# v2.net
KiCad netlist of a schematic drawn in EAGLE
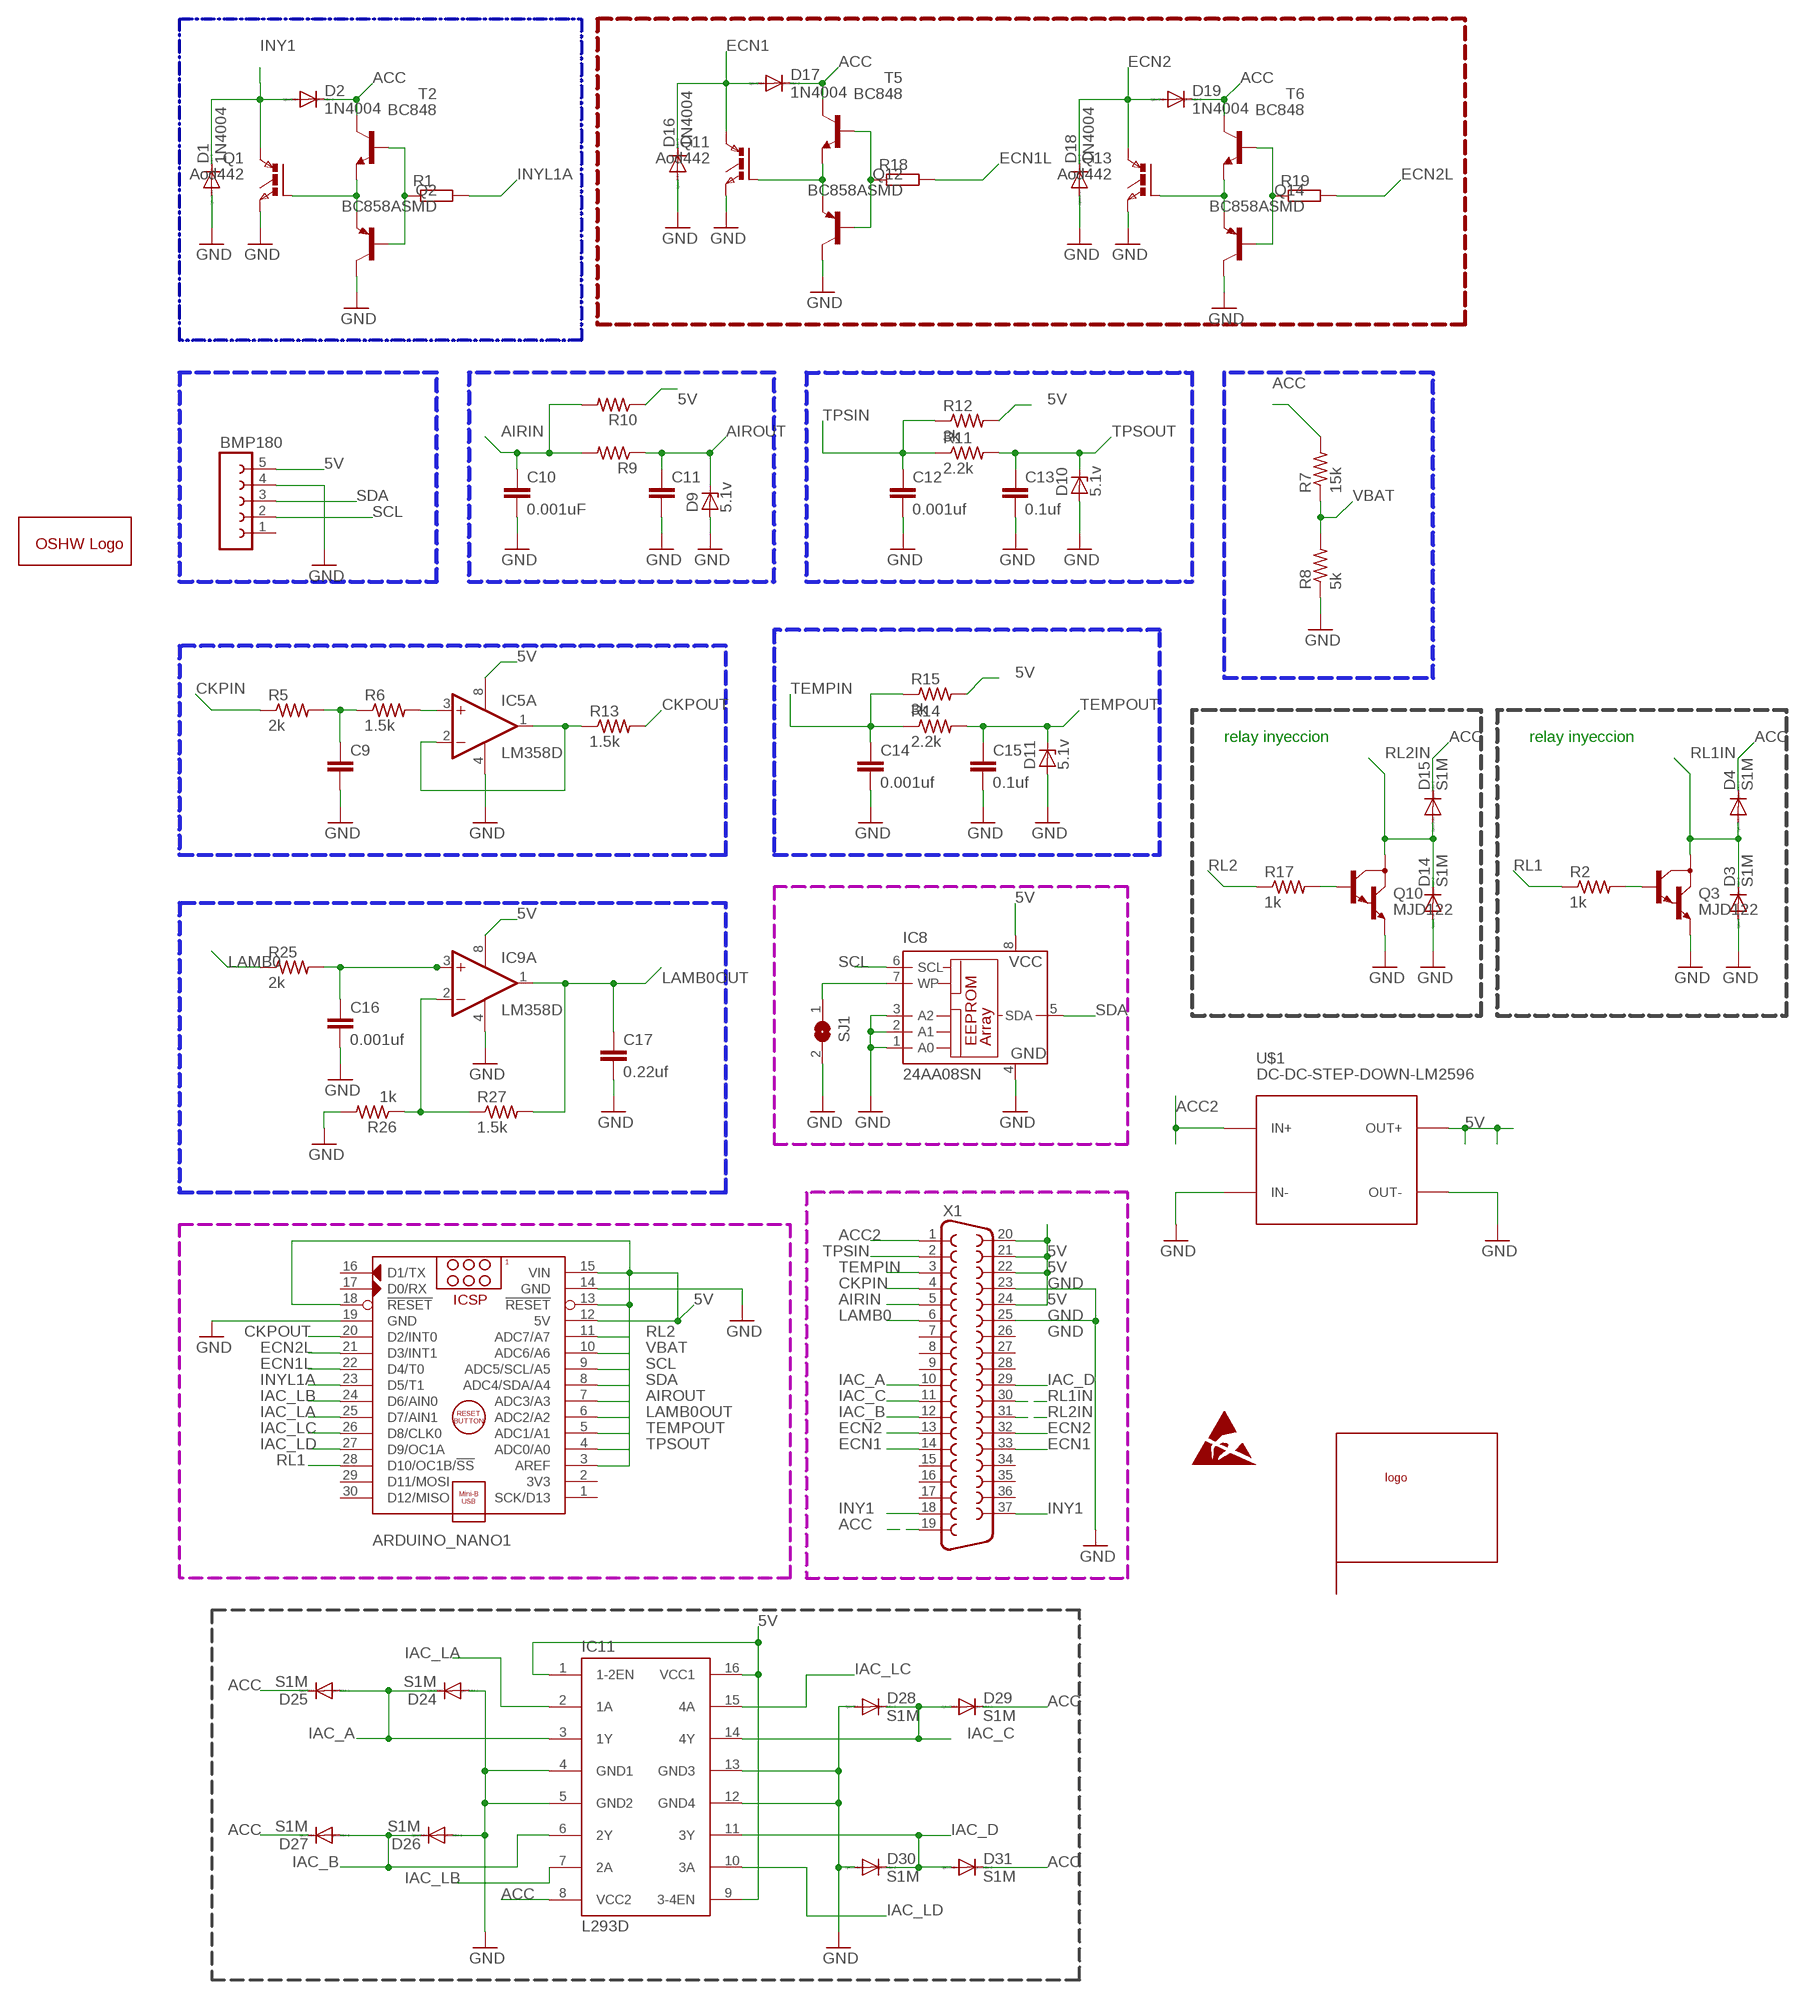
[diagram p0: schematic, sheet 1]

(export (version "E")
  (design (tool "Eeschema 10.0.6"))
  (components
    (comp (ref "ARDUINO_NANO1")
      (value "ARDUINO_NANO")
      (footprint "eagle-import:ARDUINO_NANO")
      (libsource (lib "eagle-import") (part "ARDUINO_NANO"))
    )
    (comp (ref "BMP180")
      (value "FE05-1")
      (footprint "eagle-import:FE05-1")
      (libsource (lib "eagle-import") (part "FE05-1"))
    )
    (comp (ref "C9")
      (value "C-EU025-025X050")
      (footprint "eagle-import:C025-025X050")
      (libsource (lib "eagle-import") (part "C-EU025-025X050"))
    )
    (comp (ref "C10")
      (value "0.001uF")
      (footprint "eagle-import:C025-025X050")
      (libsource (lib "eagle-import") (part "C-EU025-025X050"))
    )
    (comp (ref "C11")
      (value "C-EU025-025X050")
      (footprint "eagle-import:C025-025X050")
      (libsource (lib "eagle-import") (part "C-EU025-025X050"))
    )
    (comp (ref "C12")
      (value "0.001uf")
      (footprint "eagle-import:C025-025X050")
      (libsource (lib "eagle-import") (part "C-EU025-025X050"))
    )
    (comp (ref "C13")
      (value "0.1uf")
      (footprint "eagle-import:C025-025X050")
      (libsource (lib "eagle-import") (part "C-EU025-025X050"))
    )
    (comp (ref "C14")
      (value "0.001uf")
      (footprint "eagle-import:C025-025X050")
      (libsource (lib "eagle-import") (part "C-EU025-025X050"))
    )
    (comp (ref "C15")
      (value "0.1uf")
      (footprint "eagle-import:C025-025X050")
      (libsource (lib "eagle-import") (part "C-EU025-025X050"))
    )
    (comp (ref "C16")
      (value "0.001uf")
      (footprint "eagle-import:C025-025X050")
      (libsource (lib "eagle-import") (part "C-EU025-025X050"))
    )
    (comp (ref "C17")
      (value "0.22uf")
      (footprint "eagle-import:C025-025X050")
      (libsource (lib "eagle-import") (part "C-EU025-025X050"))
    )
    (comp (ref "D1")
      (value "1N4004")
      (footprint "eagle-import:DO41-10")
      (libsource (lib "eagle-import") (part "1N4004"))
    )
    (comp (ref "D2")
      (value "1N4004")
      (footprint "eagle-import:DO41-10")
      (libsource (lib "eagle-import") (part "1N4004"))
    )
    (comp (ref "D3")
      (value "S1M")
      (footprint "eagle-import:SMA")
      (libsource (lib "eagle-import") (part "S1M"))
    )
    (comp (ref "D4")
      (value "S1M")
      (footprint "eagle-import:SMA")
      (libsource (lib "eagle-import") (part "S1M"))
    )
    (comp (ref "D9")
      (value "5.1v")
      (footprint "eagle-import:ZDIO-5")
      (libsource (lib "eagle-import") (part "ZENER-DIODEZD-5"))
    )
    (comp (ref "D10")
      (value "5.1v")
      (footprint "eagle-import:ZDIO-5")
      (libsource (lib "eagle-import") (part "ZENER-DIODEZD-5"))
    )
    (comp (ref "D11")
      (value "5.1v")
      (footprint "eagle-import:ZDIO-5")
      (libsource (lib "eagle-import") (part "ZENER-DIODEZD-5"))
    )
    (comp (ref "D14")
      (value "S1M")
      (footprint "eagle-import:SMA")
      (libsource (lib "eagle-import") (part "S1M"))
    )
    (comp (ref "D15")
      (value "S1M")
      (footprint "eagle-import:SMA")
      (libsource (lib "eagle-import") (part "S1M"))
    )
    (comp (ref "D16")
      (value "1N4004")
      (footprint "eagle-import:DO41-10")
      (libsource (lib "eagle-import") (part "1N4004"))
    )
    (comp (ref "D17")
      (value "1N4004")
      (footprint "eagle-import:DO41-10")
      (libsource (lib "eagle-import") (part "1N4004"))
    )
    (comp (ref "D18")
      (value "1N4004")
      (footprint "eagle-import:DO41-10")
      (libsource (lib "eagle-import") (part "1N4004"))
    )
    (comp (ref "D19")
      (value "1N4004")
      (footprint "eagle-import:DO41-10")
      (libsource (lib "eagle-import") (part "1N4004"))
    )
    (comp (ref "D24")
      (value "S1M")
      (footprint "eagle-import:SMA")
      (libsource (lib "eagle-import") (part "S1M"))
    )
    (comp (ref "D25")
      (value "S1M")
      (footprint "eagle-import:SMA")
      (libsource (lib "eagle-import") (part "S1M"))
    )
    (comp (ref "D26")
      (value "S1M")
      (footprint "eagle-import:SMA")
      (libsource (lib "eagle-import") (part "S1M"))
    )
    (comp (ref "D27")
      (value "S1M")
      (footprint "eagle-import:SMA")
      (libsource (lib "eagle-import") (part "S1M"))
    )
    (comp (ref "D28")
      (value "S1M")
      (footprint "eagle-import:SMA")
      (libsource (lib "eagle-import") (part "S1M"))
    )
    (comp (ref "D29")
      (value "S1M")
      (footprint "eagle-import:SMA")
      (libsource (lib "eagle-import") (part "S1M"))
    )
    (comp (ref "D30")
      (value "S1M")
      (footprint "eagle-import:SMA")
      (libsource (lib "eagle-import") (part "S1M"))
    )
    (comp (ref "D31")
      (value "S1M")
      (footprint "eagle-import:SMA")
      (libsource (lib "eagle-import") (part "S1M"))
    )
    (comp (ref "GOLD_ORB_SM1")
      (value "OSHWLOGOLOGO8MM")
      (footprint "eagle-import:OSHW_8MM")
      (libsource (lib "eagle-import") (part "OSHWLOGOLOGO8MM"))
    )
    (comp (ref "IC5")
      (value "LM358D")
      (footprint "eagle-import:SO08")
      (libsource (lib "eagle-import") (part "LM358D"))
    )
    (comp (ref "IC8")
      (value "24AA08SN")
      (footprint "eagle-import:SO-08")
      (fields (field (name "MF") "MICROCHIP") (field (name "MPN") "24AA08-I/SN"))
      (libsource (lib "eagle-import") (part "24SNAA08"))
    )
    (comp (ref "IC9")
      (value "LM358D")
      (footprint "eagle-import:SO08")
      (libsource (lib "eagle-import") (part "LM358D"))
    )
    (comp (ref "IC11")
      (value "L293D")
      (footprint "eagle-import:DIL16")
      (libsource (lib "eagle-import") (part "L293D"))
    )
    (comp (ref "Q1")
      (value "Aod442")
      (footprint "eagle-import:TO252")
      (libsource (lib "eagle-import") (part "IGBTTO252"))
    )
    (comp (ref "Q2")
      (value "BC858ASMD")
      (footprint "eagle-import:SOT23-BEC")
      (libsource (lib "eagle-import") (part "BC858SMDA"))
    )
    (comp (ref "Q3")
      (value "MJD122")
      (footprint "eagle-import:DPAK")
      (fields (field (name "MF") "STMicroelectronics"))
      (libsource (lib "eagle-import") (part "MJD122"))
    )
    (comp (ref "Q10")
      (value "MJD122")
      (footprint "eagle-import:DPAK")
      (fields (field (name "MF") "STMicroelectronics"))
      (libsource (lib "eagle-import") (part "MJD122"))
    )
    (comp (ref "Q11")
      (value "Aod442")
      (footprint "eagle-import:TO252")
      (libsource (lib "eagle-import") (part "IGBTTO252"))
    )
    (comp (ref "Q12")
      (value "BC858ASMD")
      (footprint "eagle-import:SOT23-BEC")
      (libsource (lib "eagle-import") (part "BC858SMDA"))
    )
    (comp (ref "Q13")
      (value "Aod442")
      (footprint "eagle-import:TO252")
      (libsource (lib "eagle-import") (part "IGBTTO252"))
    )
    (comp (ref "Q14")
      (value "BC858ASMD")
      (footprint "eagle-import:SOT23-BEC")
      (libsource (lib "eagle-import") (part "BC858SMDA"))
    )
    (comp (ref "R1")
      (value "R-EU_0204/7")
      (footprint "eagle-import:0204_7")
      (libsource (lib "eagle-import") (part "R-EU_0204/7"))
    )
    (comp (ref "R2")
      (value "1k")
      (footprint "eagle-import:0204_5")
      (libsource (lib "eagle-import") (part "R-US_0204/5"))
    )
    (comp (ref "R5")
      (value "2k")
      (footprint "eagle-import:0204_5")
      (libsource (lib "eagle-import") (part "R-US_0204/5"))
    )
    (comp (ref "R6")
      (value "1.5k")
      (footprint "eagle-import:0204_5")
      (libsource (lib "eagle-import") (part "R-US_0204/5"))
    )
    (comp (ref "R7")
      (value "15k")
      (footprint "eagle-import:0204_5")
      (libsource (lib "eagle-import") (part "R-US_0204/5"))
    )
    (comp (ref "R8")
      (value "5k")
      (footprint "eagle-import:0204_5")
      (libsource (lib "eagle-import") (part "R-US_0204/5"))
    )
    (comp (ref "R9")
      (value "R-US_0204/5")
      (footprint "eagle-import:0204_5")
      (libsource (lib "eagle-import") (part "R-US_0204/5"))
    )
    (comp (ref "R10")
      (value "R-US_0204/5")
      (footprint "eagle-import:0204_5")
      (libsource (lib "eagle-import") (part "R-US_0204/5"))
    )
    (comp (ref "R11")
      (value "2.2k")
      (footprint "eagle-import:0204_5")
      (libsource (lib "eagle-import") (part "R-US_0204/5"))
    )
    (comp (ref "R12")
      (value "3k")
      (footprint "eagle-import:0204_5")
      (libsource (lib "eagle-import") (part "R-US_0204/5"))
    )
    (comp (ref "R13")
      (value "1.5k")
      (footprint "eagle-import:0204_5")
      (libsource (lib "eagle-import") (part "R-US_0204/5"))
    )
    (comp (ref "R14")
      (value "2.2k")
      (footprint "eagle-import:0204_5")
      (libsource (lib "eagle-import") (part "R-US_0204/5"))
    )
    (comp (ref "R15")
      (value "3k")
      (footprint "eagle-import:0204_5")
      (libsource (lib "eagle-import") (part "R-US_0204/5"))
    )
    (comp (ref "R17")
      (value "1k")
      (footprint "eagle-import:0204_5")
      (libsource (lib "eagle-import") (part "R-US_0204/5"))
    )
    (comp (ref "R18")
      (value "R-EU_0204/7")
      (footprint "eagle-import:0204_7")
      (libsource (lib "eagle-import") (part "R-EU_0204/7"))
    )
    (comp (ref "R19")
      (value "R-EU_0204/7")
      (footprint "eagle-import:0204_7")
      (libsource (lib "eagle-import") (part "R-EU_0204/7"))
    )
    (comp (ref "R25")
      (value "2k")
      (footprint "eagle-import:0204_5")
      (libsource (lib "eagle-import") (part "R-US_0204/5"))
    )
    (comp (ref "R26")
      (value "1k")
      (footprint "eagle-import:0204_5")
      (libsource (lib "eagle-import") (part "R-US_0204/5"))
    )
    (comp (ref "R27")
      (value "1.5k")
      (footprint "eagle-import:0204_5")
      (libsource (lib "eagle-import") (part "R-US_0204/5"))
    )
    (comp (ref "SJ1")
      (value "SJW")
      (footprint "eagle-import:SJW")
      (libsource (lib "eagle-import") (part "SJW"))
    )
    (comp (ref "T2")
      (value "BC848")
      (footprint "eagle-import:SOT23")
      (libsource (lib "eagle-import") (part "BC848"))
    )
    (comp (ref "T5")
      (value "BC848")
      (footprint "eagle-import:SOT23")
      (libsource (lib "eagle-import") (part "BC848"))
    )
    (comp (ref "T6")
      (value "BC848")
      (footprint "eagle-import:SOT23")
      (libsource (lib "eagle-import") (part "BC848"))
    )
    (comp (ref "U$1")
      (value "DC-DC-STEP-DOWN-LM2596")
      (footprint "eagle-import:DC-DC-STEP-DOWN-LM2596")
      (libsource (lib "eagle-import") (part "DC-DC-STEP-DOWN-LM2596"))
    )
    (comp (ref "U$2")
      (value "LOGO")
      (footprint "eagle-import:LOGO")
      (libsource (lib "eagle-import") (part "LOGO"))
    )
    (comp (ref "X1")
      (value "F37HP")
      (footprint "eagle-import:F37HP")
      (libsource (lib "eagle-import") (part "F37HP"))
    )
  )
  (nets
    (net (code "1") (name "/5V") (class "Default")
      (node (ref "ARDUINO_NANO1") (pin "12") (pinfunction "5V_12") (pintype "power_in"))
      (node (ref "ARDUINO_NANO1") (pin "13") (pinfunction "~{RESET}_13") (pintype "input"))
      (node (ref "ARDUINO_NANO1") (pin "15") (pinfunction "VIN_15") (pintype "power_in"))
      (node (ref "ARDUINO_NANO1") (pin "18") (pinfunction "~{RESET}_18") (pintype "input"))
      (node (ref "ARDUINO_NANO1") (pin "3") (pinfunction "AREF_3") (pintype "input"))
      (node (ref "BMP180") (pin "5") (pinfunction "5_5") (pintype "passive"))
      (node (ref "IC11") (pin "1") (pinfunction "1-2EN_1") (pintype "input"))
      (node (ref "IC11") (pin "16") (pinfunction "VCC1_16") (pintype "power_in"))
      (node (ref "IC11") (pin "9") (pinfunction "3-4EN_9") (pintype "input"))
      (node (ref "IC5") (pin "8") (pinfunction "V+_8") (pintype "power_in"))
      (node (ref "IC8") (pin "8") (pinfunction "VCC_8") (pintype "power_in"))
      (node (ref "IC9") (pin "8") (pinfunction "V+_8") (pintype "power_in"))
      (node (ref "R10") (pin "1") (pinfunction "1_1") (pintype "passive"))
      (node (ref "R12") (pin "2") (pinfunction "2_2") (pintype "passive"))
      (node (ref "R15") (pin "2") (pinfunction "2_2") (pintype "passive"))
      (node (ref "U$1") (pin "OUT+") (pinfunction "OUT+_OUT+") (pintype "bidirectional"))
      (node (ref "X1") (pin "20") (pinfunction "20_20") (pintype "passive"))
      (node (ref "X1") (pin "21") (pinfunction "21_21") (pintype "passive"))
      (node (ref "X1") (pin "22") (pinfunction "22_22") (pintype "passive"))
      (node (ref "X1") (pin "24") (pinfunction "24_24") (pintype "passive"))
    )
    (net (code "2") (name "/ACC") (class "Default")
      (node (ref "D15") (pin "C") (pinfunction "C_C") (pintype "passive"))
      (node (ref "D17") (pin "C") (pinfunction "C_C") (pintype "passive"))
      (node (ref "D19") (pin "C") (pinfunction "C_C") (pintype "passive"))
      (node (ref "D2") (pin "C") (pinfunction "C_C") (pintype "passive"))
      (node (ref "D25") (pin "C") (pinfunction "C_C") (pintype "passive"))
      (node (ref "D27") (pin "C") (pinfunction "C_C") (pintype "passive"))
      (node (ref "D29") (pin "C") (pinfunction "C_C") (pintype "passive"))
      (node (ref "D31") (pin "C") (pinfunction "C_C") (pintype "passive"))
      (node (ref "D4") (pin "C") (pinfunction "C_C") (pintype "passive"))
      (node (ref "IC11") (pin "8") (pinfunction "VCC2_8") (pintype "power_in"))
      (node (ref "R7") (pin "2") (pinfunction "2_2") (pintype "passive"))
      (node (ref "T2") (pin "3") (pinfunction "C_3") (pintype "passive"))
      (node (ref "T5") (pin "3") (pinfunction "C_3") (pintype "passive"))
      (node (ref "T6") (pin "3") (pinfunction "C_3") (pintype "passive"))
      (node (ref "X1") (pin "19") (pinfunction "19_19") (pintype "passive"))
    )
    (net (code "3") (name "/ACC2") (class "Default")
      (node (ref "U$1") (pin "IN+") (pinfunction "IN+_IN+") (pintype "bidirectional"))
      (node (ref "X1") (pin "1") (pinfunction "1_1") (pintype "passive"))
    )
    (net (code "4") (name "/AIRIN") (class "Default")
      (node (ref "C10") (pin "1") (pinfunction "1_1") (pintype "passive"))
      (node (ref "R10") (pin "2") (pinfunction "2_2") (pintype "passive"))
      (node (ref "R9") (pin "2") (pinfunction "2_2") (pintype "passive"))
      (node (ref "X1") (pin "5") (pinfunction "5_5") (pintype "passive"))
    )
    (net (code "5") (name "/AIROUT") (class "Default")
      (node (ref "ARDUINO_NANO1") (pin "7") (pinfunction "ADC3/A3_7") (pintype "bidirectional"))
      (node (ref "C11") (pin "1") (pinfunction "1_1") (pintype "passive"))
      (node (ref "D9") (pin "C") (pinfunction "C_C") (pintype "passive"))
      (node (ref "R9") (pin "1") (pinfunction "1_1") (pintype "passive"))
    )
    (net (code "6") (name "/CKPIN") (class "Default")
      (node (ref "R5") (pin "1") (pinfunction "1_1") (pintype "passive"))
      (node (ref "X1") (pin "4") (pinfunction "4_4") (pintype "passive"))
    )
    (net (code "7") (name "/CKPOUT") (class "Default")
      (node (ref "ARDUINO_NANO1") (pin "20") (pinfunction "D2/INT0_20") (pintype "bidirectional"))
      (node (ref "R13") (pin "2") (pinfunction "2_2") (pintype "passive"))
    )
    (net (code "8") (name "/ECN1") (class "Default")
      (node (ref "D16") (pin "C") (pinfunction "C_C") (pintype "passive"))
      (node (ref "D17") (pin "A") (pinfunction "A_A") (pintype "passive"))
      (node (ref "Q11") (pin "2") (pinfunction "C_2") (pintype "passive"))
      (node (ref "X1") (pin "14") (pinfunction "14_14") (pintype "passive"))
      (node (ref "X1") (pin "33") (pinfunction "33_33") (pintype "passive"))
    )
    (net (code "9") (name "/ECN1L") (class "Default")
      (node (ref "ARDUINO_NANO1") (pin "22") (pinfunction "D4/T0_22") (pintype "bidirectional"))
      (node (ref "R18") (pin "2") (pinfunction "2_2") (pintype "passive"))
    )
    (net (code "10") (name "/ECN2") (class "Default")
      (node (ref "D18") (pin "C") (pinfunction "C_C") (pintype "passive"))
      (node (ref "D19") (pin "A") (pinfunction "A_A") (pintype "passive"))
      (node (ref "Q13") (pin "2") (pinfunction "C_2") (pintype "passive"))
      (node (ref "X1") (pin "13") (pinfunction "13_13") (pintype "passive"))
      (node (ref "X1") (pin "32") (pinfunction "32_32") (pintype "passive"))
    )
    (net (code "11") (name "/ECN2L") (class "Default")
      (node (ref "ARDUINO_NANO1") (pin "21") (pinfunction "D3/INT1_21") (pintype "bidirectional"))
      (node (ref "R19") (pin "2") (pinfunction "2_2") (pintype "passive"))
    )
    (net (code "12") (name "/IAC_A") (class "Default")
      (node (ref "D24") (pin "C") (pinfunction "C_C") (pintype "passive"))
      (node (ref "D25") (pin "A") (pinfunction "A_A") (pintype "passive"))
      (node (ref "IC11") (pin "3") (pinfunction "1Y_3") (pintype "output"))
      (node (ref "X1") (pin "10") (pinfunction "10_10") (pintype "passive"))
    )
    (net (code "13") (name "/IAC_B") (class "Default")
      (node (ref "D26") (pin "C") (pinfunction "C_C") (pintype "passive"))
      (node (ref "D27") (pin "A") (pinfunction "A_A") (pintype "passive"))
      (node (ref "IC11") (pin "6") (pinfunction "2Y_6") (pintype "output"))
      (node (ref "X1") (pin "12") (pinfunction "12_12") (pintype "passive"))
    )
    (net (code "14") (name "/IAC_C") (class "Default")
      (node (ref "D28") (pin "C") (pinfunction "C_C") (pintype "passive"))
      (node (ref "D29") (pin "A") (pinfunction "A_A") (pintype "passive"))
      (node (ref "IC11") (pin "14") (pinfunction "4Y_14") (pintype "output"))
      (node (ref "X1") (pin "11") (pinfunction "11_11") (pintype "passive"))
    )
    (net (code "15") (name "/IAC_D") (class "Default")
      (node (ref "D30") (pin "C") (pinfunction "C_C") (pintype "passive"))
      (node (ref "D31") (pin "A") (pinfunction "A_A") (pintype "passive"))
      (node (ref "IC11") (pin "11") (pinfunction "3Y_11") (pintype "output"))
      (node (ref "X1") (pin "29") (pinfunction "29_29") (pintype "passive"))
    )
    (net (code "16") (name "/IAC_LA") (class "Default")
      (node (ref "ARDUINO_NANO1") (pin "25") (pinfunction "D7/AIN1_25") (pintype "bidirectional"))
      (node (ref "IC11") (pin "2") (pinfunction "1A_2") (pintype "input"))
    )
    (net (code "17") (name "/IAC_LB") (class "Default")
      (node (ref "ARDUINO_NANO1") (pin "24") (pinfunction "D6/AIN0_24") (pintype "bidirectional"))
      (node (ref "IC11") (pin "7") (pinfunction "2A_7") (pintype "input"))
    )
    (net (code "18") (name "/IAC_LC") (class "Default")
      (node (ref "ARDUINO_NANO1") (pin "26") (pinfunction "D8/CLK0_26") (pintype "bidirectional"))
      (node (ref "IC11") (pin "15") (pinfunction "4A_15") (pintype "input"))
    )
    (net (code "19") (name "/IAC_LD") (class "Default")
      (node (ref "ARDUINO_NANO1") (pin "27") (pinfunction "D9/OC1A_27") (pintype "bidirectional"))
      (node (ref "IC11") (pin "10") (pinfunction "3A_10") (pintype "input"))
    )
    (net (code "20") (name "/INY1") (class "Default")
      (node (ref "D1") (pin "C") (pinfunction "C_C") (pintype "passive"))
      (node (ref "D2") (pin "A") (pinfunction "A_A") (pintype "passive"))
      (node (ref "Q1") (pin "2") (pinfunction "C_2") (pintype "passive"))
      (node (ref "X1") (pin "18") (pinfunction "18_18") (pintype "passive"))
      (node (ref "X1") (pin "37") (pinfunction "37_37") (pintype "passive"))
    )
    (net (code "21") (name "/INYL1A") (class "Default")
      (node (ref "ARDUINO_NANO1") (pin "23") (pinfunction "D5/T1_23") (pintype "bidirectional"))
      (node (ref "R1") (pin "2") (pinfunction "2_2") (pintype "passive"))
    )
    (net (code "22") (name "/LAMB0") (class "Default")
      (node (ref "R25") (pin "1") (pinfunction "1_1") (pintype "passive"))
      (node (ref "X1") (pin "6") (pinfunction "6_6") (pintype "passive"))
    )
    (net (code "23") (name "/LAMB0OUT") (class "Default")
      (node (ref "ARDUINO_NANO1") (pin "6") (pinfunction "ADC2/A2_6") (pintype "bidirectional"))
      (node (ref "C17") (pin "1") (pinfunction "1_1") (pintype "passive"))
      (node (ref "IC9") (pin "1") (pinfunction "OUT_1") (pintype "output"))
      (node (ref "R27") (pin "2") (pinfunction "2_2") (pintype "passive"))
    )
    (net (code "24") (name "/RL1") (class "Default")
      (node (ref "ARDUINO_NANO1") (pin "28") (pinfunction "D10/OC1B/~{SS}_28") (pintype "bidirectional"))
      (node (ref "R2") (pin "1") (pinfunction "1_1") (pintype "passive"))
    )
    (net (code "25") (name "/RL1IN") (class "Default")
      (node (ref "D3") (pin "C") (pinfunction "C_C") (pintype "passive"))
      (node (ref "D4") (pin "A") (pinfunction "A_A") (pintype "passive"))
      (node (ref "Q3") (pin "4") (pinfunction "C_4") (pintype "passive"))
      (node (ref "X1") (pin "30") (pinfunction "30_30") (pintype "passive"))
    )
    (net (code "26") (name "/RL2") (class "Default")
      (node (ref "ARDUINO_NANO1") (pin "11") (pinfunction "ADC7/A7_11") (pintype "bidirectional"))
      (node (ref "R17") (pin "1") (pinfunction "1_1") (pintype "passive"))
    )
    (net (code "27") (name "/RL2IN") (class "Default")
      (node (ref "D14") (pin "C") (pinfunction "C_C") (pintype "passive"))
      (node (ref "D15") (pin "A") (pinfunction "A_A") (pintype "passive"))
      (node (ref "Q10") (pin "4") (pinfunction "C_4") (pintype "passive"))
      (node (ref "X1") (pin "31") (pinfunction "31_31") (pintype "passive"))
    )
    (net (code "28") (name "/SCL") (class "Default")
      (node (ref "ARDUINO_NANO1") (pin "9") (pinfunction "ADC5/SCL/A5_9") (pintype "bidirectional"))
      (node (ref "BMP180") (pin "2") (pinfunction "2_2") (pintype "passive"))
      (node (ref "IC8") (pin "6") (pinfunction "SCL_6") (pintype "input"))
    )
    (net (code "29") (name "/SDA") (class "Default")
      (node (ref "ARDUINO_NANO1") (pin "8") (pinfunction "ADC4/SDA/A4_8") (pintype "bidirectional"))
      (node (ref "BMP180") (pin "3") (pinfunction "3_3") (pintype "passive"))
      (node (ref "IC8") (pin "5") (pinfunction "SDA_5") (pintype "bidirectional"))
    )
    (net (code "30") (name "/TEMPIN") (class "Default")
      (node (ref "C14") (pin "1") (pinfunction "1_1") (pintype "passive"))
      (node (ref "R14") (pin "1") (pinfunction "1_1") (pintype "passive"))
      (node (ref "R15") (pin "1") (pinfunction "1_1") (pintype "passive"))
      (node (ref "X1") (pin "3") (pinfunction "3_3") (pintype "passive"))
    )
    (net (code "31") (name "/TEMPOUT") (class "Default")
      (node (ref "ARDUINO_NANO1") (pin "5") (pinfunction "ADC1/A1_5") (pintype "bidirectional"))
      (node (ref "C15") (pin "1") (pinfunction "1_1") (pintype "passive"))
      (node (ref "D11") (pin "C") (pinfunction "C_C") (pintype "passive"))
      (node (ref "R14") (pin "2") (pinfunction "2_2") (pintype "passive"))
    )
    (net (code "32") (name "/TPSIN") (class "Default")
      (node (ref "C12") (pin "1") (pinfunction "1_1") (pintype "passive"))
      (node (ref "R11") (pin "1") (pinfunction "1_1") (pintype "passive"))
      (node (ref "R12") (pin "1") (pinfunction "1_1") (pintype "passive"))
      (node (ref "X1") (pin "2") (pinfunction "2_2") (pintype "passive"))
    )
    (net (code "33") (name "/TPSOUT") (class "Default")
      (node (ref "ARDUINO_NANO1") (pin "4") (pinfunction "ADC0/A0_4") (pintype "bidirectional"))
      (node (ref "C13") (pin "1") (pinfunction "1_1") (pintype "passive"))
      (node (ref "D10") (pin "C") (pinfunction "C_C") (pintype "passive"))
      (node (ref "R11") (pin "2") (pinfunction "2_2") (pintype "passive"))
    )
    (net (code "34") (name "/VBAT") (class "Default")
      (node (ref "ARDUINO_NANO1") (pin "10") (pinfunction "ADC6/A6_10") (pintype "bidirectional"))
      (node (ref "R7") (pin "1") (pinfunction "1_1") (pintype "passive"))
      (node (ref "R8") (pin "2") (pinfunction "2_2") (pintype "passive"))
    )
    (net (code "35") (name "GND") (class "Default")
      (node (ref "ARDUINO_NANO1") (pin "14") (pinfunction "GND_14") (pintype "power_in"))
      (node (ref "ARDUINO_NANO1") (pin "19") (pinfunction "GND_19") (pintype "power_in"))
      (node (ref "BMP180") (pin "4") (pinfunction "4_4") (pintype "passive"))
      (node (ref "C10") (pin "2") (pinfunction "2_2") (pintype "passive"))
      (node (ref "C11") (pin "2") (pinfunction "2_2") (pintype "passive"))
      (node (ref "C12") (pin "2") (pinfunction "2_2") (pintype "passive"))
      (node (ref "C13") (pin "2") (pinfunction "2_2") (pintype "passive"))
      (node (ref "C14") (pin "2") (pinfunction "2_2") (pintype "passive"))
      (node (ref "C15") (pin "2") (pinfunction "2_2") (pintype "passive"))
      (node (ref "C16") (pin "2") (pinfunction "2_2") (pintype "passive"))
      (node (ref "C17") (pin "2") (pinfunction "2_2") (pintype "passive"))
      (node (ref "C9") (pin "2") (pinfunction "2_2") (pintype "passive"))
      (node (ref "D1") (pin "A") (pinfunction "A_A") (pintype "passive"))
      (node (ref "D10") (pin "A") (pinfunction "A_A") (pintype "passive"))
      (node (ref "D11") (pin "A") (pinfunction "A_A") (pintype "passive"))
      (node (ref "D14") (pin "A") (pinfunction "A_A") (pintype "passive"))
      (node (ref "D16") (pin "A") (pinfunction "A_A") (pintype "passive"))
      (node (ref "D18") (pin "A") (pinfunction "A_A") (pintype "passive"))
      (node (ref "D24") (pin "A") (pinfunction "A_A") (pintype "passive"))
      (node (ref "D26") (pin "A") (pinfunction "A_A") (pintype "passive"))
      (node (ref "D28") (pin "A") (pinfunction "A_A") (pintype "passive"))
      (node (ref "D3") (pin "A") (pinfunction "A_A") (pintype "passive"))
      (node (ref "D30") (pin "A") (pinfunction "A_A") (pintype "passive"))
      (node (ref "D9") (pin "A") (pinfunction "A_A") (pintype "passive"))
      (node (ref "IC11") (pin "12") (pinfunction "GND4_12") (pintype "power_in"))
      (node (ref "IC11") (pin "13") (pinfunction "GND3_13") (pintype "power_in"))
      (node (ref "IC11") (pin "4") (pinfunction "GND1_4") (pintype "power_in"))
      (node (ref "IC11") (pin "5") (pinfunction "GND2_5") (pintype "power_in"))
      (node (ref "IC5") (pin "4") (pinfunction "V-_4") (pintype "power_in"))
      (node (ref "IC8") (pin "1") (pinfunction "A0_1") (pintype "input"))
      (node (ref "IC8") (pin "2") (pinfunction "A1_2") (pintype "input"))
      (node (ref "IC8") (pin "3") (pinfunction "A2_3") (pintype "input"))
      (node (ref "IC8") (pin "4") (pinfunction "GND_4") (pintype "power_in"))
      (node (ref "IC9") (pin "4") (pinfunction "V-_4") (pintype "power_in"))
      (node (ref "Q1") (pin "3") (pinfunction "E_3") (pintype "passive"))
      (node (ref "Q10") (pin "3") (pinfunction "E_3") (pintype "passive"))
      (node (ref "Q11") (pin "3") (pinfunction "E_3") (pintype "passive"))
      (node (ref "Q12") (pin "C") (pinfunction "C_C") (pintype "passive"))
      (node (ref "Q13") (pin "3") (pinfunction "E_3") (pintype "passive"))
      (node (ref "Q14") (pin "C") (pinfunction "C_C") (pintype "passive"))
      (node (ref "Q2") (pin "C") (pinfunction "C_C") (pintype "passive"))
      (node (ref "Q3") (pin "3") (pinfunction "E_3") (pintype "passive"))
      (node (ref "R26") (pin "2") (pinfunction "2_2") (pintype "passive"))
      (node (ref "R8") (pin "1") (pinfunction "1_1") (pintype "passive"))
      (node (ref "SJ1") (pin "2") (pinfunction "2_2") (pintype "passive"))
      (node (ref "U$1") (pin "IN-") (pinfunction "IN-_IN-") (pintype "bidirectional"))
      (node (ref "U$1") (pin "OUT-") (pinfunction "OUT-_OUT-") (pintype "bidirectional"))
      (node (ref "X1") (pin "23") (pinfunction "23_23") (pintype "passive"))
      (node (ref "X1") (pin "25") (pinfunction "25_25") (pintype "passive"))
    )
    (net (code "36") (name "Net-(C9-Pad1)") (class "Default")
      (node (ref "C9") (pin "1") (pinfunction "1_1") (pintype "passive"))
      (node (ref "R5") (pin "2") (pinfunction "2_2") (pintype "passive"))
      (node (ref "R6") (pin "1") (pinfunction "1_1") (pintype "passive"))
    )
    (net (code "37") (name "Net-(IC5A-+IN)") (class "Default")
      (node (ref "IC5") (pin "3") (pinfunction "+IN_3") (pintype "input"))
      (node (ref "R6") (pin "2") (pinfunction "2_2") (pintype "passive"))
    )
    (net (code "38") (name "Net-(IC5A--IN)") (class "Default")
      (node (ref "IC5") (pin "1") (pinfunction "OUT_1") (pintype "output"))
      (node (ref "IC5") (pin "2") (pinfunction "-IN_2") (pintype "input"))
      (node (ref "R13") (pin "1") (pinfunction "1_1") (pintype "passive"))
    )
    (net (code "39") (name "Net-(IC8-WP)") (class "Default")
      (node (ref "IC8") (pin "7") (pinfunction "WP_7") (pintype "input"))
      (node (ref "SJ1") (pin "1") (pinfunction "1_1") (pintype "passive"))
    )
    (net (code "40") (name "Net-(IC9A-+IN)") (class "Default")
      (node (ref "C16") (pin "1") (pinfunction "1_1") (pintype "passive"))
      (node (ref "IC9") (pin "3") (pinfunction "+IN_3") (pintype "input"))
      (node (ref "R25") (pin "2") (pinfunction "2_2") (pintype "passive"))
    )
    (net (code "41") (name "Net-(IC9A--IN)") (class "Default")
      (node (ref "IC9") (pin "2") (pinfunction "-IN_2") (pintype "input"))
      (node (ref "R26") (pin "1") (pinfunction "1_1") (pintype "passive"))
      (node (ref "R27") (pin "1") (pinfunction "1_1") (pintype "passive"))
    )
    (net (code "42") (name "Net-(Q1-G)") (class "Default")
      (node (ref "Q1") (pin "1") (pinfunction "G_1") (pintype "passive"))
      (node (ref "Q2") (pin "E") (pinfunction "E_E") (pintype "passive"))
      (node (ref "T2") (pin "2") (pinfunction "E_2") (pintype "passive"))
    )
    (net (code "43") (name "Net-(Q3-B)") (class "Default")
      (node (ref "Q3") (pin "1") (pinfunction "B_1") (pintype "passive"))
      (node (ref "R2") (pin "2") (pinfunction "2_2") (pintype "passive"))
    )
    (net (code "44") (name "Net-(Q10-B)") (class "Default")
      (node (ref "Q10") (pin "1") (pinfunction "B_1") (pintype "passive"))
      (node (ref "R17") (pin "2") (pinfunction "2_2") (pintype "passive"))
    )
    (net (code "45") (name "Net-(Q11-G)") (class "Default")
      (node (ref "Q11") (pin "1") (pinfunction "G_1") (pintype "passive"))
      (node (ref "Q12") (pin "E") (pinfunction "E_E") (pintype "passive"))
      (node (ref "T5") (pin "2") (pinfunction "E_2") (pintype "passive"))
    )
    (net (code "46") (name "Net-(Q13-G)") (class "Default")
      (node (ref "Q13") (pin "1") (pinfunction "G_1") (pintype "passive"))
      (node (ref "Q14") (pin "E") (pinfunction "E_E") (pintype "passive"))
      (node (ref "T6") (pin "2") (pinfunction "E_2") (pintype "passive"))
    )
    (net (code "47") (name "Net-(T2-B)") (class "Default")
      (node (ref "Q2") (pin "B") (pinfunction "B_B") (pintype "passive"))
      (node (ref "R1") (pin "1") (pinfunction "1_1") (pintype "passive"))
      (node (ref "T2") (pin "1") (pinfunction "B_1") (pintype "passive"))
    )
    (net (code "48") (name "Net-(T5-B)") (class "Default")
      (node (ref "Q12") (pin "B") (pinfunction "B_B") (pintype "passive"))
      (node (ref "R18") (pin "1") (pinfunction "1_1") (pintype "passive"))
      (node (ref "T5") (pin "1") (pinfunction "B_1") (pintype "passive"))
    )
    (net (code "49") (name "Net-(T6-B)") (class "Default")
      (node (ref "Q14") (pin "B") (pinfunction "B_B") (pintype "passive"))
      (node (ref "R19") (pin "1") (pinfunction "1_1") (pintype "passive"))
      (node (ref "T6") (pin "1") (pinfunction "B_1") (pintype "passive"))
    )
    (net (code "50") (name "unconnected-(ARDUINO_NANO1-3V3-Pad2)") (class "Default")
      (node (ref "ARDUINO_NANO1") (pin "2") (pinfunction "3V3_2") (pintype "output"))
    )
    (net (code "51") (name "unconnected-(ARDUINO_NANO1-D0{slash}RX-Pad17)") (class "Default")
      (node (ref "ARDUINO_NANO1") (pin "17") (pinfunction "D0/RX_17") (pintype "bidirectional"))
    )
    (net (code "52") (name "unconnected-(ARDUINO_NANO1-D1{slash}TX-Pad16)") (class "Default")
      (node (ref "ARDUINO_NANO1") (pin "16") (pinfunction "D1/TX_16") (pintype "bidirectional"))
    )
    (net (code "53") (name "unconnected-(ARDUINO_NANO1-D11{slash}MOSI-Pad29)") (class "Default")
      (node (ref "ARDUINO_NANO1") (pin "29") (pinfunction "D11/MOSI_29") (pintype "bidirectional"))
    )
    (net (code "54") (name "unconnected-(ARDUINO_NANO1-D12{slash}MISO-Pad30)") (class "Default")
      (node (ref "ARDUINO_NANO1") (pin "30") (pinfunction "D12/MISO_30") (pintype "bidirectional"))
    )
    (net (code "55") (name "unconnected-(ARDUINO_NANO1-SCK{slash}D13-Pad1)") (class "Default")
      (node (ref "ARDUINO_NANO1") (pin "1") (pinfunction "SCK/D13_1") (pintype "bidirectional"))
    )
    (net (code "56") (name "unconnected-(BMP180-Pad1)") (class "Default")
      (node (ref "BMP180") (pin "1") (pinfunction "1_1") (pintype "passive"))
    )
    (net (code "57") (name "unconnected-(X1-Pad7)") (class "Default")
      (node (ref "X1") (pin "7") (pinfunction "7_7") (pintype "passive"))
    )
    (net (code "58") (name "unconnected-(X1-Pad8)") (class "Default")
      (node (ref "X1") (pin "8") (pinfunction "8_8") (pintype "passive"))
    )
    (net (code "59") (name "unconnected-(X1-Pad9)") (class "Default")
      (node (ref "X1") (pin "9") (pinfunction "9_9") (pintype "passive"))
    )
    (net (code "60") (name "unconnected-(X1-Pad15)") (class "Default")
      (node (ref "X1") (pin "15") (pinfunction "15_15") (pintype "passive"))
    )
    (net (code "61") (name "unconnected-(X1-Pad16)") (class "Default")
      (node (ref "X1") (pin "16") (pinfunction "16_16") (pintype "passive"))
    )
    (net (code "62") (name "unconnected-(X1-Pad17)") (class "Default")
      (node (ref "X1") (pin "17") (pinfunction "17_17") (pintype "passive"))
    )
    (net (code "63") (name "unconnected-(X1-Pad26)") (class "Default")
      (node (ref "X1") (pin "26") (pinfunction "26_26") (pintype "passive"))
    )
    (net (code "64") (name "unconnected-(X1-Pad27)") (class "Default")
      (node (ref "X1") (pin "27") (pinfunction "27_27") (pintype "passive"))
    )
    (net (code "65") (name "unconnected-(X1-Pad28)") (class "Default")
      (node (ref "X1") (pin "28") (pinfunction "28_28") (pintype "passive"))
    )
    (net (code "66") (name "unconnected-(X1-Pad34)") (class "Default")
      (node (ref "X1") (pin "34") (pinfunction "34_34") (pintype "passive"))
    )
    (net (code "67") (name "unconnected-(X1-Pad35)") (class "Default")
      (node (ref "X1") (pin "35") (pinfunction "35_35") (pintype "passive"))
    )
    (net (code "68") (name "unconnected-(X1-Pad36)") (class "Default")
      (node (ref "X1") (pin "36") (pinfunction "36_36") (pintype "passive"))
    )
  )
)
